# Module32Switches_TH.net
KiCad netlist of a schematic drawn in EasyEDA Pro
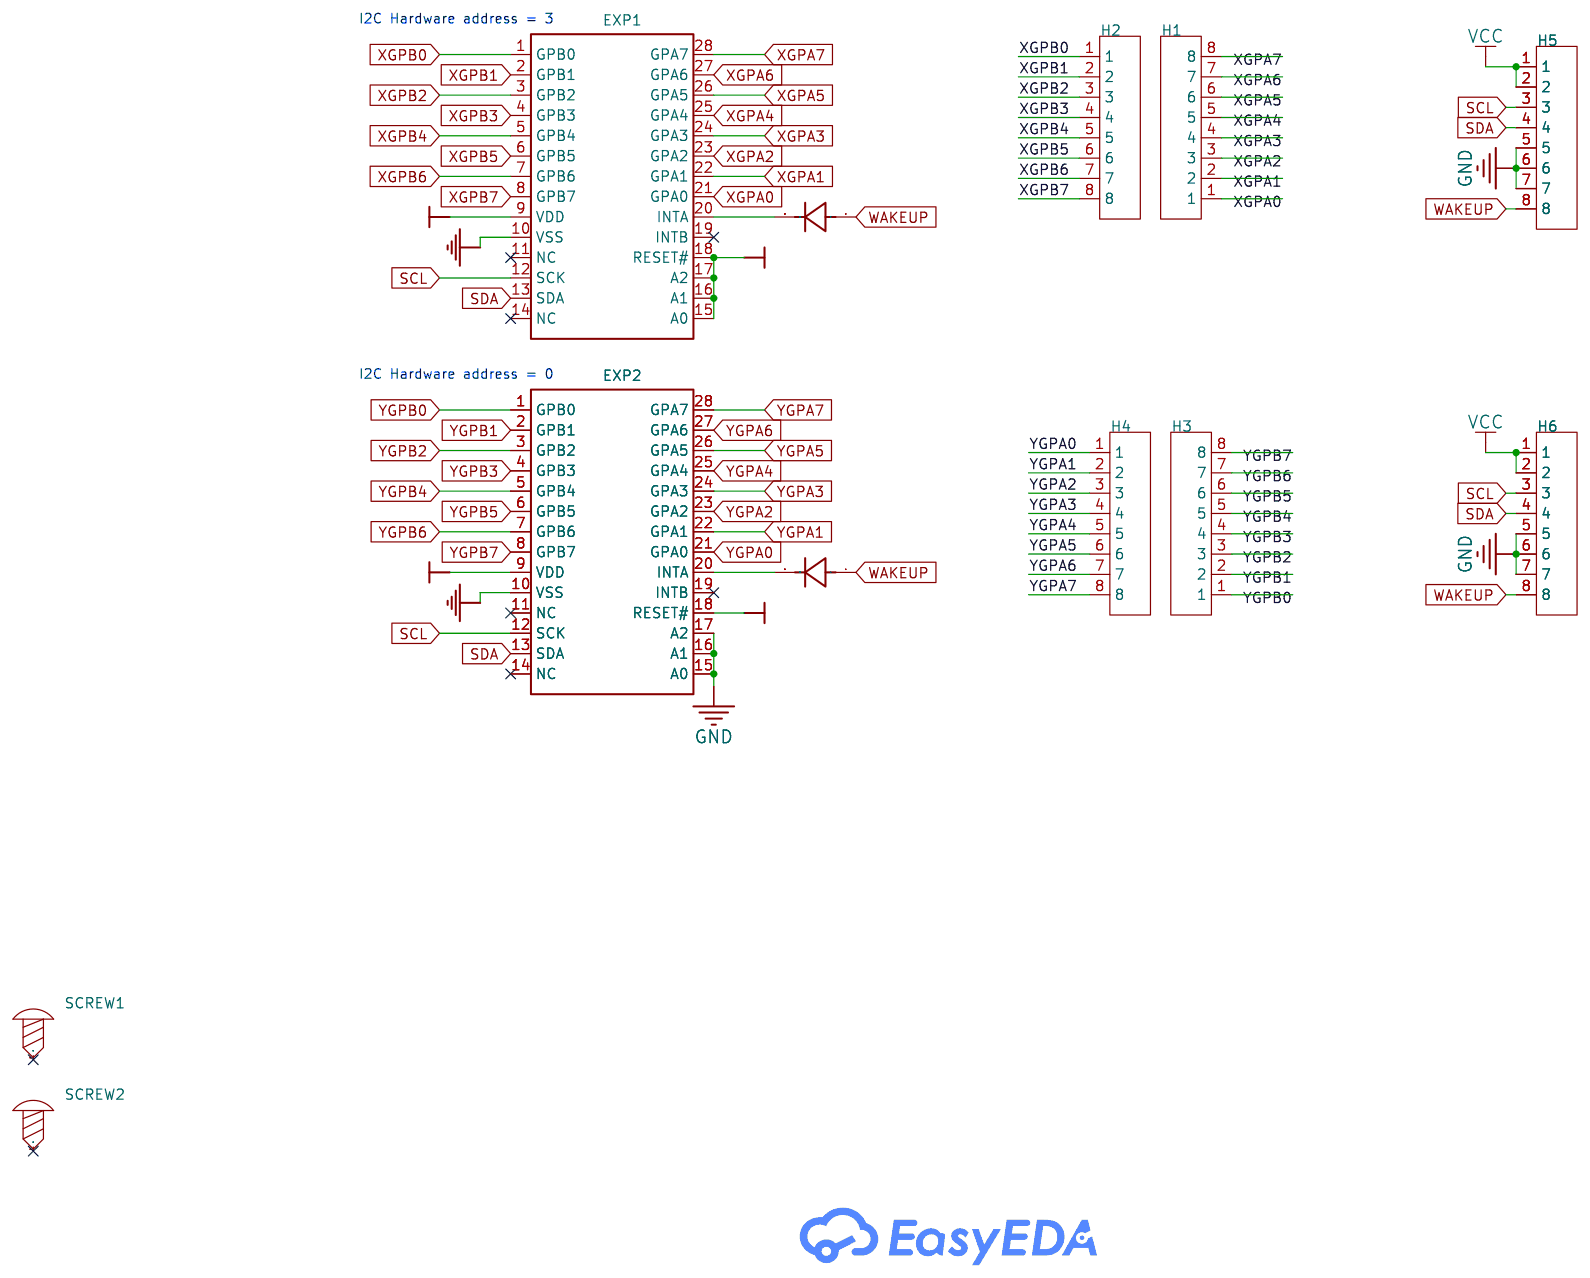
[diagram p0: schematic sheet]

(export (version "E")
  (design (tool "Eeschema 10.0.6"))
  (components
    (comp (ref "D1")
      (value "1N4148_C18195411")
      (footprint "easyedapro:DO-35_BD2.2-L4.0-D0.50_1N4148")
      (fields
        (field (name "Manufacturer Part") "1N4148")
        (field (name "Manufacturer") "LJ(朗捷)")
        (field (name "Contributor") "lcsc")
      )
      (libsource (lib "easyedapro") (part "1N4148_C18195411"))
    )
    (comp (ref "D2")
      (value "1N4148_C18195411")
      (footprint "easyedapro:DO-35_BD2.2-L4.0-D0.50_1N4148")
      (fields
        (field (name "Manufacturer Part") "1N4148")
        (field (name "Manufacturer") "LJ(朗捷)")
        (field (name "Contributor") "lcsc")
      )
      (libsource (lib "easyedapro") (part "1N4148_C18195411"))
    )
    (comp (ref "EXP1")
      (value "MCP23017-E/SP")
      (footprint "easyedapro:DIP-28_L34.6-W7.3-P2.54-LS10.2-BL")
      (fields (field (name "Manufacturer") "MICROCHIP(美国微芯)") (field (name "Contributor") "LCSC"))
      (libsource (lib "easyedapro") (part "MCP23017-E/SP"))
    )
    (comp (ref "EXP2")
      (value "MCP23017-E/SP")
      (footprint "easyedapro:DIP-28_L34.6-W7.3-P2.54-LS10.2-BL")
      (fields (field (name "Manufacturer") "MICROCHIP(美国微芯)") (field (name "Contributor") "LCSC"))
      (libsource (lib "easyedapro") (part "MCP23017-E/SP"))
    )
    (comp (ref "H1")
      (value "PZ254R-11-08P")
      (footprint "easyedapro:HDR-TH_8P-P2.54-H-M-W10.4")
      (fields (field (name "Manufacturer") "XFCN(兴飞)"))
      (libsource (lib "easyedapro") (part "PZ254R-11-08P"))
    )
    (comp (ref "H2")
      (value "PZ254R-11-08P")
      (footprint "easyedapro:HDR-TH_8P-P2.54-H-M-W10.4")
      (fields (field (name "Manufacturer") "XFCN(兴飞)"))
      (libsource (lib "easyedapro") (part "PZ254R-11-08P"))
    )
    (comp (ref "H3")
      (value "PZ254R-11-08P")
      (footprint "easyedapro:HDR-TH_8P-P2.54-H-M-W10.4")
      (fields (field (name "Manufacturer") "XFCN(兴飞)"))
      (libsource (lib "easyedapro") (part "PZ254R-11-08P"))
    )
    (comp (ref "H4")
      (value "PZ254R-11-08P")
      (footprint "easyedapro:HDR-TH_8P-P2.54-H-M-W10.4")
      (fields (field (name "Manufacturer") "XFCN(兴飞)"))
      (libsource (lib "easyedapro") (part "PZ254R-11-08P"))
    )
    (comp (ref "H5")
      (value "PZ254R-11-08P")
      (footprint "easyedapro:HDR-TH_8P-P2.54-H-M-W10.4")
      (fields (field (name "Manufacturer") "XFCN(兴飞)"))
      (libsource (lib "easyedapro") (part "PZ254R-11-08P"))
    )
    (comp (ref "H6")
      (value "PZ254R-11-08P")
      (footprint "easyedapro:HDR-TH_8P-P2.54-H-M-W10.4")
      (fields (field (name "Manufacturer") "XFCN(兴飞)"))
      (libsource (lib "easyedapro") (part "PZ254R-11-08P"))
    )
    (comp (ref "SCREW1")
      (value "~")
      (footprint "easyedapro:Screw-Hole-M2")
      (libsource (lib "easyedapro") (part "Screw-Hole"))
    )
    (comp (ref "SCREW2")
      (value "~")
      (footprint "easyedapro:Screw-Hole-M2")
      (libsource (lib "easyedapro") (part "Screw-Hole"))
    )
  )
  (nets
    (net (code "1") (name "GND") (class "Default")
      (node (ref "EXP1") (pin "10") (pinfunction "VSS_10") (pintype "unspecified"))
      (node (ref "EXP2") (pin "10") (pinfunction "VSS_10") (pintype "unspecified"))
      (node (ref "EXP2") (pin "15") (pinfunction "A0_15") (pintype "unspecified"))
      (node (ref "EXP2") (pin "16") (pinfunction "A1_16") (pintype "unspecified"))
      (node (ref "EXP2") (pin "17") (pinfunction "A2_17") (pintype "unspecified"))
      (node (ref "H5") (pin "5") (pinfunction "5_5") (pintype "unspecified"))
      (node (ref "H5") (pin "6") (pinfunction "6_6") (pintype "unspecified"))
      (node (ref "H5") (pin "7") (pinfunction "7_7") (pintype "unspecified"))
      (node (ref "H6") (pin "5") (pinfunction "5_5") (pintype "unspecified"))
      (node (ref "H6") (pin "6") (pinfunction "6_6") (pintype "unspecified"))
      (node (ref "H6") (pin "7") (pinfunction "7_7") (pintype "unspecified"))
    )
    (net (code "2") (name "Net-(D1-C)") (class "Default")
      (node (ref "D1") (pin "2") (pinfunction "C_2") (pintype "unspecified"))
      (node (ref "EXP1") (pin "20") (pinfunction "INTA_20") (pintype "unspecified"))
    )
    (net (code "3") (name "Net-(D2-C)") (class "Default")
      (node (ref "D2") (pin "2") (pinfunction "C_2") (pintype "unspecified"))
      (node (ref "EXP2") (pin "20") (pinfunction "INTA_20") (pintype "unspecified"))
    )
    (net (code "4") (name "SCL") (class "Default")
      (node (ref "EXP1") (pin "12") (pinfunction "SCK_12") (pintype "unspecified"))
      (node (ref "EXP2") (pin "12") (pinfunction "SCK_12") (pintype "unspecified"))
      (node (ref "H5") (pin "3") (pinfunction "3_3") (pintype "unspecified"))
      (node (ref "H6") (pin "3") (pinfunction "3_3") (pintype "unspecified"))
    )
    (net (code "5") (name "SDA") (class "Default")
      (node (ref "EXP1") (pin "13") (pinfunction "SDA_13") (pintype "unspecified"))
      (node (ref "EXP2") (pin "13") (pinfunction "SDA_13") (pintype "unspecified"))
      (node (ref "H5") (pin "4") (pinfunction "4_4") (pintype "unspecified"))
      (node (ref "H6") (pin "4") (pinfunction "4_4") (pintype "unspecified"))
    )
    (net (code "6") (name "VCC") (class "Default")
      (node (ref "EXP1") (pin "15") (pinfunction "A0_15") (pintype "unspecified"))
      (node (ref "EXP1") (pin "16") (pinfunction "A1_16") (pintype "unspecified"))
      (node (ref "EXP1") (pin "17") (pinfunction "A2_17") (pintype "unspecified"))
      (node (ref "EXP1") (pin "18") (pinfunction "RESET#_18") (pintype "unspecified"))
      (node (ref "EXP1") (pin "9") (pinfunction "VDD_9") (pintype "unspecified"))
      (node (ref "EXP2") (pin "18") (pinfunction "RESET#_18") (pintype "unspecified"))
      (node (ref "EXP2") (pin "9") (pinfunction "VDD_9") (pintype "unspecified"))
      (node (ref "H5") (pin "1") (pinfunction "1_1") (pintype "unspecified"))
      (node (ref "H5") (pin "2") (pinfunction "2_2") (pintype "unspecified"))
      (node (ref "H6") (pin "1") (pinfunction "1_1") (pintype "unspecified"))
      (node (ref "H6") (pin "2") (pinfunction "2_2") (pintype "unspecified"))
    )
    (net (code "7") (name "WAKEUP") (class "Default")
      (node (ref "D1") (pin "1") (pinfunction "A_1") (pintype "unspecified"))
      (node (ref "D2") (pin "1") (pinfunction "A_1") (pintype "unspecified"))
      (node (ref "H5") (pin "8") (pinfunction "8_8") (pintype "unspecified"))
      (node (ref "H6") (pin "8") (pinfunction "8_8") (pintype "unspecified"))
    )
    (net (code "8") (name "XGPA0") (class "Default")
      (node (ref "EXP1") (pin "21") (pinfunction "GPA0_21") (pintype "unspecified"))
      (node (ref "H1") (pin "1") (pinfunction "1_1") (pintype "unspecified"))
    )
    (net (code "9") (name "XGPA1") (class "Default")
      (node (ref "EXP1") (pin "22") (pinfunction "GPA1_22") (pintype "unspecified"))
      (node (ref "H1") (pin "2") (pinfunction "2_2") (pintype "unspecified"))
    )
    (net (code "10") (name "XGPA2") (class "Default")
      (node (ref "EXP1") (pin "23") (pinfunction "GPA2_23") (pintype "unspecified"))
      (node (ref "H1") (pin "3") (pinfunction "3_3") (pintype "unspecified"))
    )
    (net (code "11") (name "XGPA3") (class "Default")
      (node (ref "EXP1") (pin "24") (pinfunction "GPA3_24") (pintype "unspecified"))
      (node (ref "H1") (pin "4") (pinfunction "4_4") (pintype "unspecified"))
    )
    (net (code "12") (name "XGPA4") (class "Default")
      (node (ref "EXP1") (pin "25") (pinfunction "GPA4_25") (pintype "unspecified"))
      (node (ref "H1") (pin "5") (pinfunction "5_5") (pintype "unspecified"))
    )
    (net (code "13") (name "XGPA5") (class "Default")
      (node (ref "EXP1") (pin "26") (pinfunction "GPA5_26") (pintype "unspecified"))
      (node (ref "H1") (pin "6") (pinfunction "6_6") (pintype "unspecified"))
    )
    (net (code "14") (name "XGPA6") (class "Default")
      (node (ref "EXP1") (pin "27") (pinfunction "GPA6_27") (pintype "unspecified"))
      (node (ref "H1") (pin "7") (pinfunction "7_7") (pintype "unspecified"))
    )
    (net (code "15") (name "XGPA7") (class "Default")
      (node (ref "EXP1") (pin "28") (pinfunction "GPA7_28") (pintype "unspecified"))
      (node (ref "H1") (pin "8") (pinfunction "8_8") (pintype "unspecified"))
    )
    (net (code "16") (name "XGPB0") (class "Default")
      (node (ref "EXP1") (pin "1") (pinfunction "GPB0_1") (pintype "unspecified"))
      (node (ref "H2") (pin "1") (pinfunction "1_1") (pintype "unspecified"))
    )
    (net (code "17") (name "XGPB1") (class "Default")
      (node (ref "EXP1") (pin "2") (pinfunction "GPB1_2") (pintype "unspecified"))
      (node (ref "H2") (pin "2") (pinfunction "2_2") (pintype "unspecified"))
    )
    (net (code "18") (name "XGPB2") (class "Default")
      (node (ref "EXP1") (pin "3") (pinfunction "GPB2_3") (pintype "unspecified"))
      (node (ref "H2") (pin "3") (pinfunction "3_3") (pintype "unspecified"))
    )
    (net (code "19") (name "XGPB3") (class "Default")
      (node (ref "EXP1") (pin "4") (pinfunction "GPB3_4") (pintype "unspecified"))
      (node (ref "H2") (pin "4") (pinfunction "4_4") (pintype "unspecified"))
    )
    (net (code "20") (name "XGPB4") (class "Default")
      (node (ref "EXP1") (pin "5") (pinfunction "GPB4_5") (pintype "unspecified"))
      (node (ref "H2") (pin "5") (pinfunction "5_5") (pintype "unspecified"))
    )
    (net (code "21") (name "XGPB5") (class "Default")
      (node (ref "EXP1") (pin "6") (pinfunction "GPB5_6") (pintype "unspecified"))
      (node (ref "H2") (pin "6") (pinfunction "6_6") (pintype "unspecified"))
    )
    (net (code "22") (name "XGPB6") (class "Default")
      (node (ref "EXP1") (pin "7") (pinfunction "GPB6_7") (pintype "unspecified"))
      (node (ref "H2") (pin "7") (pinfunction "7_7") (pintype "unspecified"))
    )
    (net (code "23") (name "XGPB7") (class "Default")
      (node (ref "EXP1") (pin "8") (pinfunction "GPB7_8") (pintype "unspecified"))
      (node (ref "H2") (pin "8") (pinfunction "8_8") (pintype "unspecified"))
    )
    (net (code "24") (name "YGPA0") (class "Default")
      (node (ref "EXP2") (pin "21") (pinfunction "GPA0_21") (pintype "unspecified"))
      (node (ref "H4") (pin "1") (pinfunction "1_1") (pintype "unspecified"))
    )
    (net (code "25") (name "YGPA1") (class "Default")
      (node (ref "EXP2") (pin "22") (pinfunction "GPA1_22") (pintype "unspecified"))
      (node (ref "H4") (pin "2") (pinfunction "2_2") (pintype "unspecified"))
    )
    (net (code "26") (name "YGPA2") (class "Default")
      (node (ref "EXP2") (pin "23") (pinfunction "GPA2_23") (pintype "unspecified"))
      (node (ref "H4") (pin "3") (pinfunction "3_3") (pintype "unspecified"))
    )
    (net (code "27") (name "YGPA3") (class "Default")
      (node (ref "EXP2") (pin "24") (pinfunction "GPA3_24") (pintype "unspecified"))
      (node (ref "H4") (pin "4") (pinfunction "4_4") (pintype "unspecified"))
    )
    (net (code "28") (name "YGPA4") (class "Default")
      (node (ref "EXP2") (pin "25") (pinfunction "GPA4_25") (pintype "unspecified"))
      (node (ref "H4") (pin "5") (pinfunction "5_5") (pintype "unspecified"))
    )
    (net (code "29") (name "YGPA5") (class "Default")
      (node (ref "EXP2") (pin "26") (pinfunction "GPA5_26") (pintype "unspecified"))
      (node (ref "H4") (pin "6") (pinfunction "6_6") (pintype "unspecified"))
    )
    (net (code "30") (name "YGPA6") (class "Default")
      (node (ref "EXP2") (pin "27") (pinfunction "GPA6_27") (pintype "unspecified"))
      (node (ref "H4") (pin "7") (pinfunction "7_7") (pintype "unspecified"))
    )
    (net (code "31") (name "YGPA7") (class "Default")
      (node (ref "EXP2") (pin "28") (pinfunction "GPA7_28") (pintype "unspecified"))
      (node (ref "H4") (pin "8") (pinfunction "8_8") (pintype "unspecified"))
    )
    (net (code "32") (name "YGPB0") (class "Default")
      (node (ref "EXP2") (pin "1") (pinfunction "GPB0_1") (pintype "unspecified"))
      (node (ref "H3") (pin "1") (pinfunction "1_1") (pintype "unspecified"))
    )
    (net (code "33") (name "YGPB1") (class "Default")
      (node (ref "EXP2") (pin "2") (pinfunction "GPB1_2") (pintype "unspecified"))
      (node (ref "H3") (pin "2") (pinfunction "2_2") (pintype "unspecified"))
    )
    (net (code "34") (name "YGPB2") (class "Default")
      (node (ref "EXP2") (pin "3") (pinfunction "GPB2_3") (pintype "unspecified"))
      (node (ref "H3") (pin "3") (pinfunction "3_3") (pintype "unspecified"))
    )
    (net (code "35") (name "YGPB3") (class "Default")
      (node (ref "EXP2") (pin "4") (pinfunction "GPB3_4") (pintype "unspecified"))
      (node (ref "H3") (pin "4") (pinfunction "4_4") (pintype "unspecified"))
    )
    (net (code "36") (name "YGPB4") (class "Default")
      (node (ref "EXP2") (pin "5") (pinfunction "GPB4_5") (pintype "unspecified"))
      (node (ref "H3") (pin "5") (pinfunction "5_5") (pintype "unspecified"))
    )
    (net (code "37") (name "YGPB5") (class "Default")
      (node (ref "EXP2") (pin "6") (pinfunction "GPB5_6") (pintype "unspecified"))
      (node (ref "H3") (pin "6") (pinfunction "6_6") (pintype "unspecified"))
    )
    (net (code "38") (name "YGPB6") (class "Default")
      (node (ref "EXP2") (pin "7") (pinfunction "GPB6_7") (pintype "unspecified"))
      (node (ref "H3") (pin "7") (pinfunction "7_7") (pintype "unspecified"))
    )
    (net (code "39") (name "YGPB7") (class "Default")
      (node (ref "EXP2") (pin "8") (pinfunction "GPB7_8") (pintype "unspecified"))
      (node (ref "H3") (pin "8") (pinfunction "8_8") (pintype "unspecified"))
    )
    (net (code "40") (name "unconnected-(EXP1-INTB-Pad19)") (class "Default")
      (node (ref "EXP1") (pin "19") (pinfunction "INTB_19") (pintype "unspecified+no_connect"))
    )
    (net (code "41") (name "unconnected-(EXP1-NC-Pad11)") (class "Default")
      (node (ref "EXP1") (pin "11") (pinfunction "NC_11") (pintype "unspecified+no_connect"))
    )
    (net (code "42") (name "unconnected-(EXP1-NC-Pad14)") (class "Default")
      (node (ref "EXP1") (pin "14") (pinfunction "NC_14") (pintype "unspecified+no_connect"))
    )
    (net (code "43") (name "unconnected-(EXP2-INTB-Pad19)") (class "Default")
      (node (ref "EXP2") (pin "19") (pinfunction "INTB_19") (pintype "unspecified+no_connect"))
    )
    (net (code "44") (name "unconnected-(EXP2-NC-Pad11)") (class "Default")
      (node (ref "EXP2") (pin "11") (pinfunction "NC_11") (pintype "unspecified+no_connect"))
    )
    (net (code "45") (name "unconnected-(EXP2-NC-Pad14)") (class "Default")
      (node (ref "EXP2") (pin "14") (pinfunction "NC_14") (pintype "unspecified+no_connect"))
    )
    (net (code "46") (name "unconnected-(SCREW1-Pad1)") (class "Default")
      (node (ref "SCREW1") (pin "1") (pinfunction "1_1") (pintype "input+no_connect"))
    )
    (net (code "47") (name "unconnected-(SCREW2-Pad1)") (class "Default")
      (node (ref "SCREW2") (pin "1") (pinfunction "1_1") (pintype "input+no_connect"))
    )
  )
)
